# Transcievers.net
KiCad netlist of a schematic drawn in Altium Designer
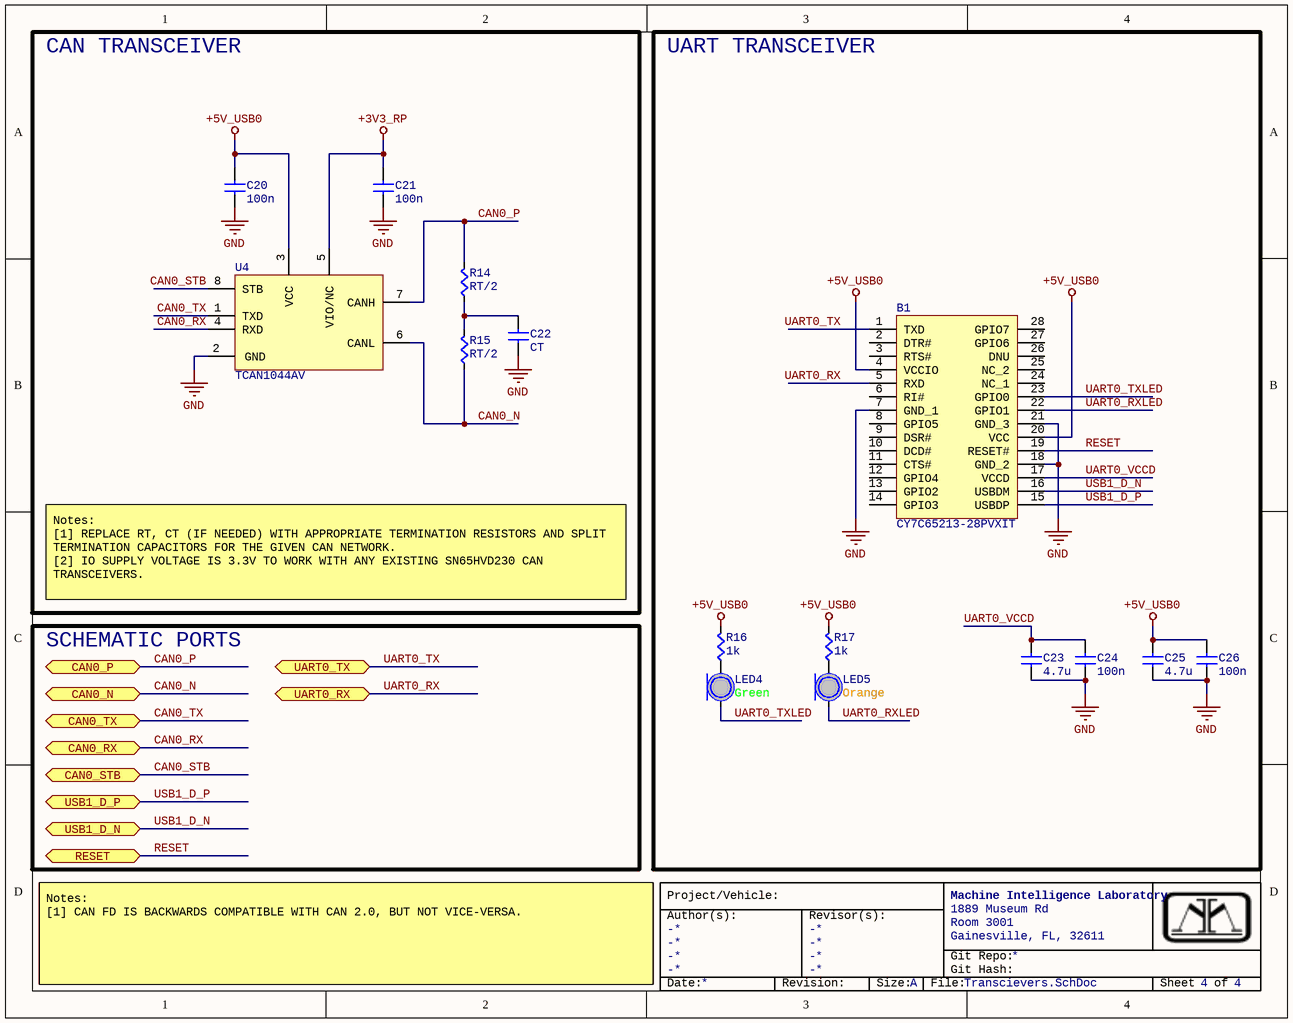
[diagram p0: Transcievers.SchDoc]

(export (version "E")
  (design (tool "Eeschema 10.0.6"))
  (components
    (comp (ref "B1")
      (value "CY7C65213-28PVXIT")
      (footprint "SOP65P780X200-28N")
      (description "USB Interface IC 32KB USB-UART LP Bridge Controller")
      (fields (field (name "MOUSER PART NUMBER") "727-CY7C6521328PVXIT"))
      (libsource (lib "TGIS_Microcontrollers") (part "CY7C65213-28PVXIT"))
    )
    (comp (ref "C20")
      (value "100n")
      (footprint "CAPC0805")
      (fields (field (name "Comment") "Cap"))
      (libsource (lib "Passives") (part "Cap"))
    )
    (comp (ref "C21")
      (value "100n")
      (footprint "CAPC0805")
      (fields (field (name "Comment") "Cap"))
      (libsource (lib "Passives") (part "Cap"))
    )
    (comp (ref "C22")
      (value "CT")
      (footprint "CAPC0805")
      (fields (field (name "Comment") "Cap"))
      (libsource (lib "Passives") (part "Cap"))
    )
    (comp (ref "C23")
      (value "4.7u")
      (footprint "CAPC0805")
      (fields (field (name "Comment") "Cap"))
      (libsource (lib "Passives") (part "Cap"))
    )
    (comp (ref "C24")
      (value "100n")
      (footprint "CAPC0805")
      (fields (field (name "Comment") "Cap"))
      (libsource (lib "Passives") (part "Cap"))
    )
    (comp (ref "C25")
      (value "4.7u")
      (footprint "CAPC0805")
      (fields (field (name "Comment") "Cap"))
      (libsource (lib "Passives") (part "Cap"))
    )
    (comp (ref "C26")
      (value "100n")
      (footprint "CAPC0805")
      (fields (field (name "Comment") "Cap"))
      (libsource (lib "Passives") (part "Cap"))
    )
    (comp (ref "LED4")
      (value "LED")
      (footprint "LED0603")
      (fields (field (name "COLOR") "Green"))
      (libsource (lib "Semiconductors") (part "LED"))
    )
    (comp (ref "LED5")
      (value "LED")
      (footprint "LED0603")
      (fields (field (name "COLOR") "Orange"))
      (libsource (lib "Semiconductors") (part "LED"))
    )
    (comp (ref "R14")
      (value "RT/2")
      (footprint "RES0603")
      (fields (field (name "Comment") "Res"))
      (libsource (lib "Passives") (part "Res"))
    )
    (comp (ref "R15")
      (value "RT/2")
      (footprint "RES0603")
      (fields (field (name "Comment") "Res"))
      (libsource (lib "Passives") (part "Res"))
    )
    (comp (ref "R16")
      (value "1k")
      (footprint "RES0603")
      (fields (field (name "Comment") "Res"))
      (libsource (lib "Passives") (part "Res"))
    )
    (comp (ref "R17")
      (value "1k")
      (footprint "RES0603")
      (fields (field (name "Comment") "Res"))
      (libsource (lib "Passives") (part "Res"))
    )
    (comp (ref "U4")
      (value "TCAN1044AV")
      (footprint "SOT65P280X110-8N")
      (description "1/1 Transceiver Half CANbus TSOT-23-8")
      (libsource (lib "TGIS_Microcontrollers") (part "TCAN1044AVDDFRQ1"))
    )
  )
  (nets
    (net (code "1") (name "+3V3_RP") (class "Default")
      (node (ref "C21") (pin "1") (pinfunction "A_1") (pintype "passive"))
      (node (ref "U4") (pin "5") (pinfunction "VIO/NC_5") (pintype "passive"))
    )
    (net (code "2") (name "+5V_USB0") (class "Default")
      (node (ref "B1") (pin "20") (pinfunction "VCC_20") (pintype "passive"))
      (node (ref "B1") (pin "4") (pinfunction "VCCIO_4") (pintype "passive"))
      (node (ref "C20") (pin "1") (pinfunction "A_1") (pintype "passive"))
      (node (ref "C25") (pin "1") (pinfunction "A_1") (pintype "passive"))
      (node (ref "C26") (pin "1") (pinfunction "A_1") (pintype "passive"))
      (node (ref "R16") (pin "1") (pinfunction "A_1") (pintype "passive"))
      (node (ref "R17") (pin "1") (pinfunction "A_1") (pintype "passive"))
      (node (ref "U4") (pin "3") (pinfunction "VCC_3") (pintype "passive"))
    )
    (net (code "3") (name "/CAN0_N") (class "Default")
      (node (ref "R15") (pin "2") (pinfunction "B_2") (pintype "passive"))
      (node (ref "U4") (pin "6") (pinfunction "CANL_6") (pintype "passive"))
    )
    (net (code "4") (name "/CAN0_P") (class "Default")
      (node (ref "R14") (pin "1") (pinfunction "A_1") (pintype "passive"))
      (node (ref "U4") (pin "7") (pinfunction "CANH_7") (pintype "passive"))
    )
    (net (code "5") (name "/CAN0_RX") (class "Default")
      (node (ref "U4") (pin "4") (pinfunction "RXD_4") (pintype "passive"))
    )
    (net (code "6") (name "/CAN0_STB") (class "Default")
      (node (ref "U4") (pin "8") (pinfunction "STB_8") (pintype "passive"))
    )
    (net (code "7") (name "/CAN0_TX") (class "Default")
      (node (ref "U4") (pin "1") (pinfunction "TXD_1") (pintype "passive"))
    )
    (net (code "8") (name "/RESET") (class "Default")
      (node (ref "B1") (pin "19") (pinfunction "RESET#_19") (pintype "passive"))
    )
    (net (code "9") (name "/UART0_RX") (class "Default")
      (node (ref "B1") (pin "5") (pinfunction "RXD_5") (pintype "passive"))
    )
    (net (code "10") (name "/UART0_RXLED") (class "Default")
      (node (ref "B1") (pin "22") (pinfunction "GPIO1_22") (pintype "passive"))
      (node (ref "LED5") (pin "C") (pinfunction "C_C") (pintype "passive"))
    )
    (net (code "11") (name "/UART0_TX") (class "Default")
      (node (ref "B1") (pin "1") (pinfunction "TXD_1") (pintype "passive"))
    )
    (net (code "12") (name "/UART0_TXLED") (class "Default")
      (node (ref "B1") (pin "23") (pinfunction "GPIO0_23") (pintype "passive"))
      (node (ref "LED4") (pin "C") (pinfunction "C_C") (pintype "passive"))
    )
    (net (code "13") (name "/UART0_VCCD") (class "Default")
      (node (ref "B1") (pin "17") (pinfunction "VCCD_17") (pintype "passive"))
      (node (ref "C23") (pin "1") (pinfunction "A_1") (pintype "passive"))
      (node (ref "C24") (pin "1") (pinfunction "A_1") (pintype "passive"))
    )
    (net (code "14") (name "/USB1_D_N") (class "Default")
      (node (ref "B1") (pin "16") (pinfunction "USBDM_16") (pintype "passive"))
    )
    (net (code "15") (name "/USB1_D_P") (class "Default")
      (node (ref "B1") (pin "15") (pinfunction "USBDP_15") (pintype "passive"))
    )
    (net (code "16") (name "GND") (class "Default")
      (node (ref "B1") (pin "18") (pinfunction "GND_2_18") (pintype "passive"))
      (node (ref "B1") (pin "21") (pinfunction "GND_3_21") (pintype "passive"))
      (node (ref "B1") (pin "7") (pinfunction "GND_1_7") (pintype "passive"))
      (node (ref "C20") (pin "2") (pinfunction "B_2") (pintype "passive"))
      (node (ref "C21") (pin "2") (pinfunction "B_2") (pintype "passive"))
      (node (ref "C22") (pin "2") (pinfunction "B_2") (pintype "passive"))
      (node (ref "C23") (pin "2") (pinfunction "B_2") (pintype "passive"))
      (node (ref "C24") (pin "2") (pinfunction "B_2") (pintype "passive"))
      (node (ref "C25") (pin "2") (pinfunction "B_2") (pintype "passive"))
      (node (ref "C26") (pin "2") (pinfunction "B_2") (pintype "passive"))
      (node (ref "U4") (pin "2") (pinfunction "GND_2") (pintype "passive"))
    )
    (net (code "17") (name "Net-(C22-A)") (class "Default")
      (node (ref "C22") (pin "1") (pinfunction "A_1") (pintype "passive"))
      (node (ref "R14") (pin "2") (pinfunction "B_2") (pintype "passive"))
      (node (ref "R15") (pin "1") (pinfunction "A_1") (pintype "passive"))
    )
    (net (code "18") (name "Net-(R16-B)") (class "Default")
      (node (ref "LED4") (pin "A") (pinfunction "A_A") (pintype "passive"))
      (node (ref "R16") (pin "2") (pinfunction "B_2") (pintype "passive"))
    )
    (net (code "19") (name "Net-(R17-B)") (class "Default")
      (node (ref "LED5") (pin "A") (pinfunction "A_A") (pintype "passive"))
      (node (ref "R17") (pin "2") (pinfunction "B_2") (pintype "passive"))
    )
    (net (code "20") (name "unconnected-(B1-CTS#-Pad11)") (class "Default")
      (node (ref "B1") (pin "11") (pinfunction "CTS#_11") (pintype "passive"))
    )
    (net (code "21") (name "unconnected-(B1-DCD#-Pad10)") (class "Default")
      (node (ref "B1") (pin "10") (pinfunction "DCD#_10") (pintype "passive"))
    )
    (net (code "22") (name "unconnected-(B1-DNU-Pad26)") (class "Default")
      (node (ref "B1") (pin "26") (pinfunction "DNU_26") (pintype "passive"))
    )
    (net (code "23") (name "unconnected-(B1-DSR#-Pad9)") (class "Default")
      (node (ref "B1") (pin "9") (pinfunction "DSR#_9") (pintype "passive"))
    )
    (net (code "24") (name "unconnected-(B1-DTR#-Pad2)") (class "Default")
      (node (ref "B1") (pin "2") (pinfunction "DTR#_2") (pintype "passive"))
    )
    (net (code "25") (name "unconnected-(B1-GPIO2-Pad13)") (class "Default")
      (node (ref "B1") (pin "13") (pinfunction "GPIO2_13") (pintype "passive"))
    )
    (net (code "26") (name "unconnected-(B1-GPIO3-Pad14)") (class "Default")
      (node (ref "B1") (pin "14") (pinfunction "GPIO3_14") (pintype "passive"))
    )
    (net (code "27") (name "unconnected-(B1-GPIO4-Pad12)") (class "Default")
      (node (ref "B1") (pin "12") (pinfunction "GPIO4_12") (pintype "passive"))
    )
    (net (code "28") (name "unconnected-(B1-GPIO5-Pad8)") (class "Default")
      (node (ref "B1") (pin "8") (pinfunction "GPIO5_8") (pintype "passive"))
    )
    (net (code "29") (name "unconnected-(B1-GPIO6-Pad27)") (class "Default")
      (node (ref "B1") (pin "27") (pinfunction "GPIO6_27") (pintype "passive"))
    )
    (net (code "30") (name "unconnected-(B1-GPIO7-Pad28)") (class "Default")
      (node (ref "B1") (pin "28") (pinfunction "GPIO7_28") (pintype "passive"))
    )
    (net (code "31") (name "unconnected-(B1-NC_1-Pad24)") (class "Default")
      (node (ref "B1") (pin "24") (pinfunction "NC_1_24") (pintype "passive"))
    )
    (net (code "32") (name "unconnected-(B1-NC_2-Pad25)") (class "Default")
      (node (ref "B1") (pin "25") (pinfunction "NC_2_25") (pintype "passive"))
    )
    (net (code "33") (name "unconnected-(B1-RI#-Pad6)") (class "Default")
      (node (ref "B1") (pin "6") (pinfunction "RI#_6") (pintype "passive"))
    )
    (net (code "34") (name "unconnected-(B1-RTS#-Pad3)") (class "Default")
      (node (ref "B1") (pin "3") (pinfunction "RTS#_3") (pintype "passive"))
    )
  )
)
